# CODEC_1_OUTPUT_BUFFER.net
KiCad netlist of a schematic drawn in Altium Designer
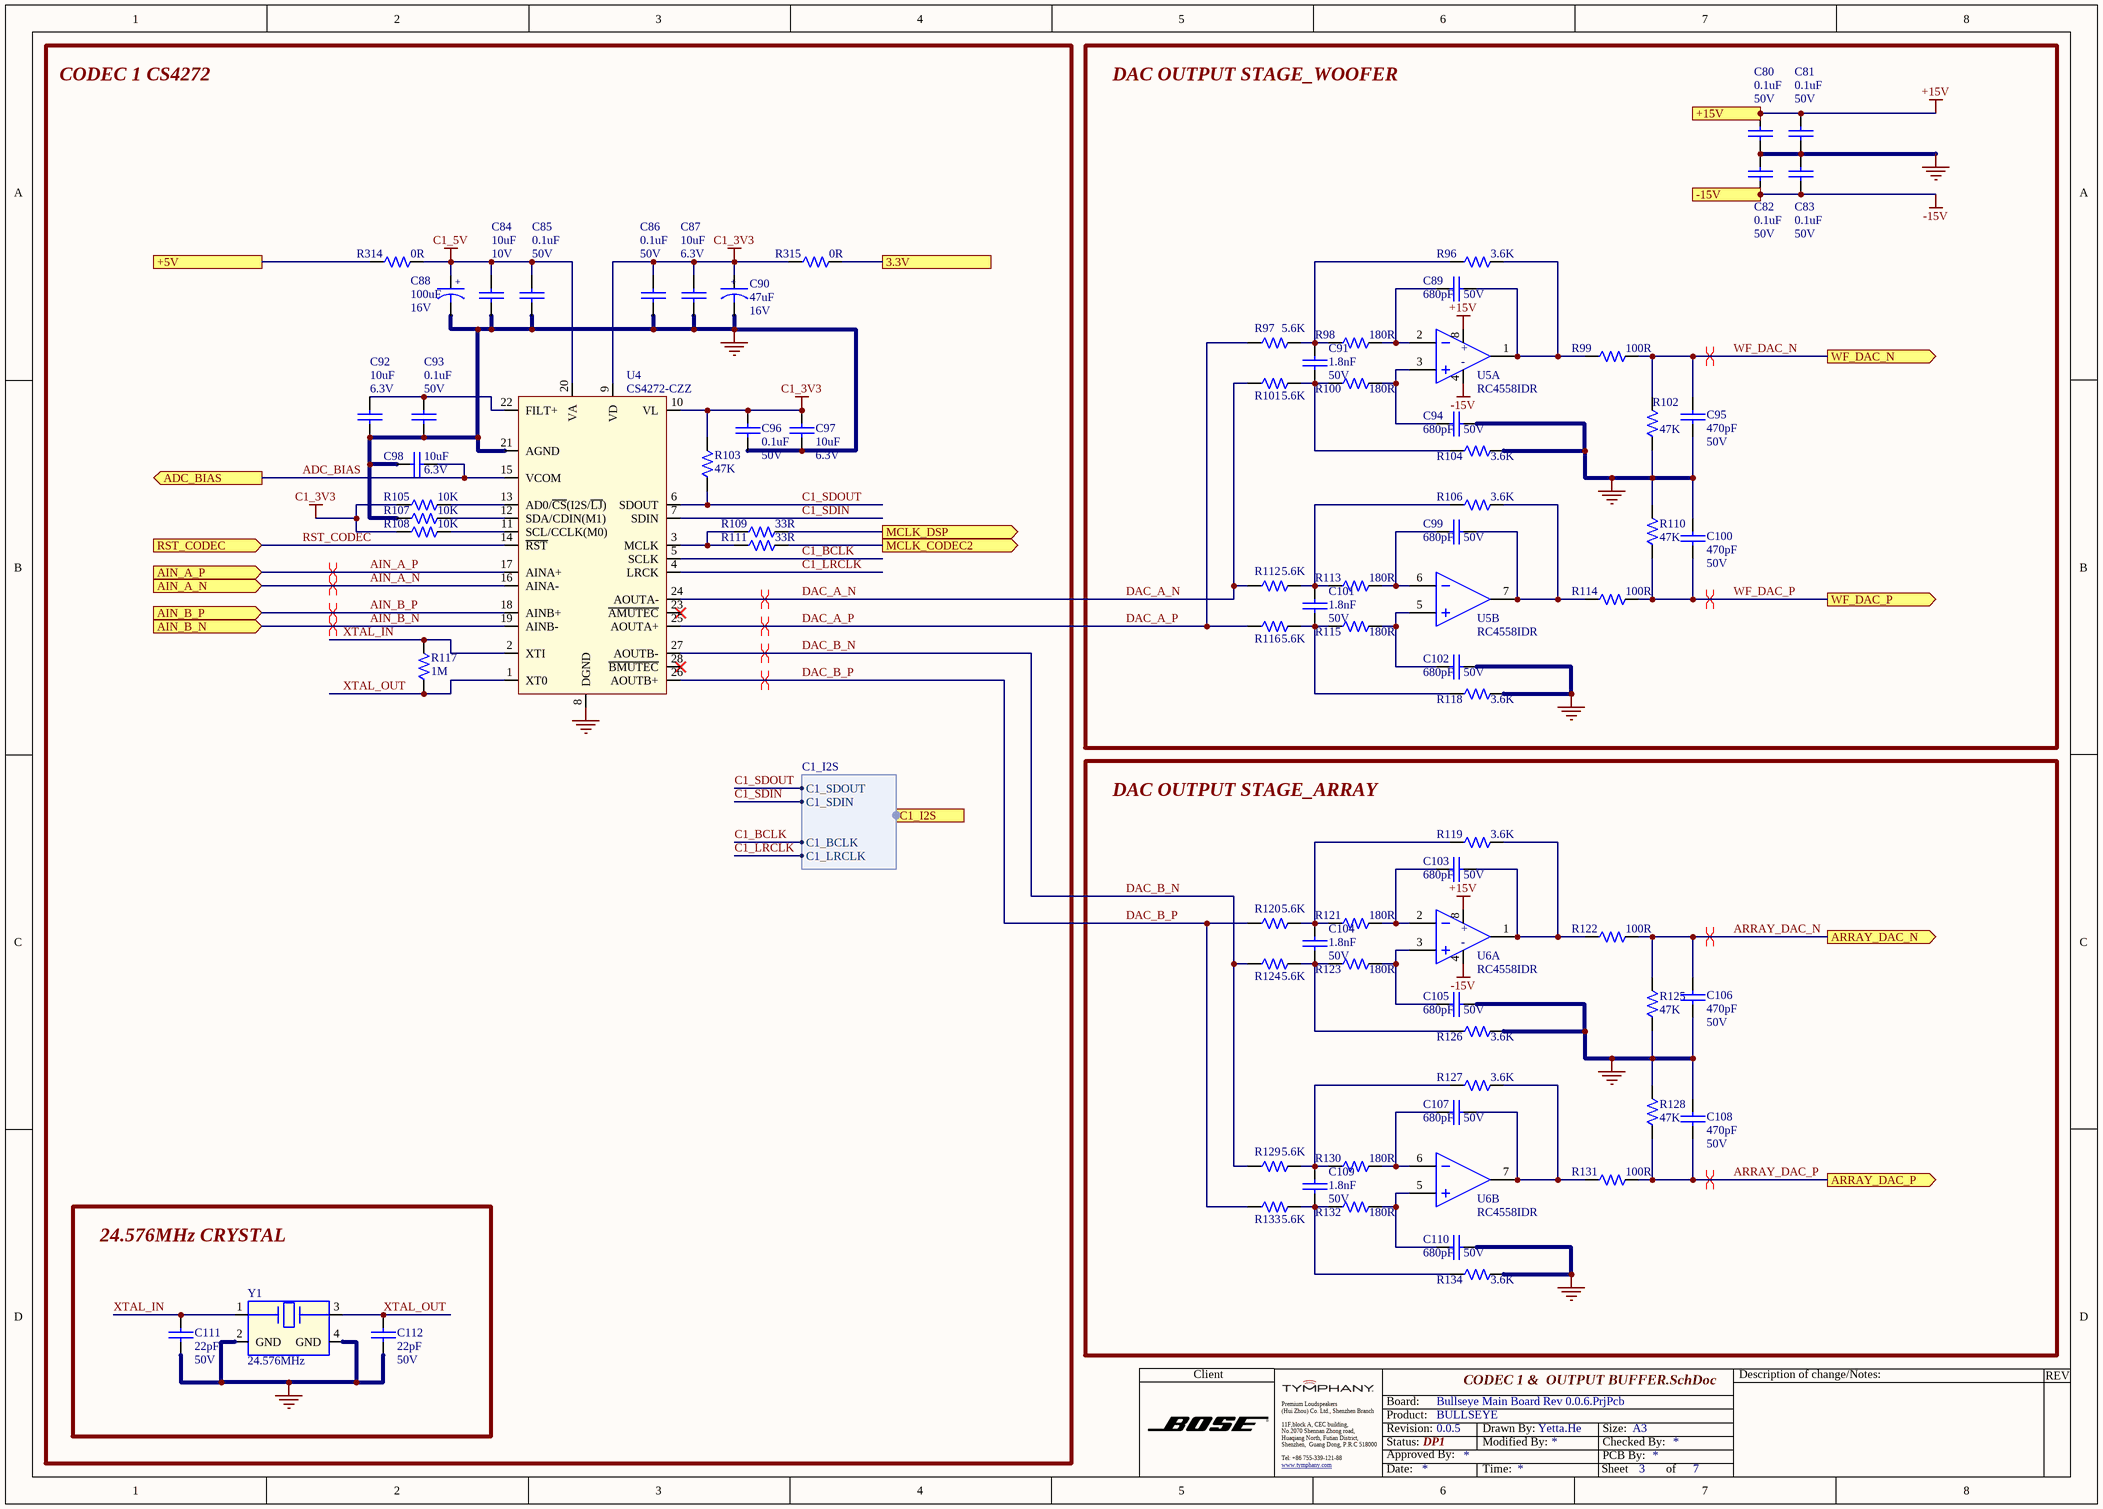
[diagram p0: CODEC 1 &  OUTPUT BUFFER.SchDoc]

(export (version "E")
  (design (tool "Eeschema 10.0.6"))
  (components
    (comp (ref "C80")
      (value "0.1uF")
      (footprint "CAPC0402-RW")
      (description "CAP, CER, 0.1uF, 10%, 50V, X7R, 0402, RoHS")
      (fields
        (field (name "TOLERANCE") "10%")
        (field (name "VOLTAGE") "50V")
        (field (name "Comment") "PWL456470-1040")
        (field (name "CREATE_NAME") "TOM@Deftronics")
      )
      (libsource (lib "P-Capacitors") (part "CAP0402 0.1uF 50V 10%"))
    )
    (comp (ref "C81")
      (value "0.1uF")
      (footprint "CAPC0402-RW")
      (description "CAP, CER, 0.1uF, 10%, 50V, X7R, 0402, RoHS")
      (fields
        (field (name "TOLERANCE") "10%")
        (field (name "VOLTAGE") "50V")
        (field (name "Comment") "PWL456470-1040")
        (field (name "CREATE_NAME") "TOM@Deftronics")
      )
      (libsource (lib "P-Capacitors") (part "CAP0402 0.1uF 50V 10%"))
    )
    (comp (ref "C82")
      (value "0.1uF")
      (footprint "CAPC0402-RW")
      (description "CAP, CER, 0.1uF, 10%, 50V, X7R, 0402, RoHS")
      (fields
        (field (name "TOLERANCE") "10%")
        (field (name "VOLTAGE") "50V")
        (field (name "Comment") "PWL456470-1040")
        (field (name "CREATE_NAME") "TOM@Deftronics")
      )
      (libsource (lib "P-Capacitors") (part "CAP0402 0.1uF 50V 10%"))
    )
    (comp (ref "C83")
      (value "0.1uF")
      (footprint "CAPC0402-RW")
      (description "CAP, CER, 0.1uF, 10%, 50V, X7R, 0402, RoHS")
      (fields
        (field (name "TOLERANCE") "10%")
        (field (name "VOLTAGE") "50V")
        (field (name "Comment") "PWL456470-1040")
        (field (name "CREATE_NAME") "TOM@Deftronics")
      )
      (libsource (lib "P-Capacitors") (part "CAP0402 0.1uF 50V 10%"))
    )
    (comp (ref "C84")
      (value "10uF")
      (footprint "CAPC0603-RW")
      (description "CAP 10UF 10V +-20% 0603X5R SAMSUNG L")
      (fields
        (field (name "MFG") "SAMSUNG")
        (field (name "TOLERANCE") "20%,")
        (field (name "VOLTAGE") "10V")
        (field (name "CREATE_NAME") "Nathan")
      )
      (libsource (lib "P-Capacitors") (part "CAP0603 10uF 10V 20%_X5R_SAMSUNG"))
    )
    (comp (ref "C85")
      (value "0.1uF")
      (footprint "CAPC0402-RW")
      (description "CAP X7R .10UF 50V +-10% 0402 WALSIN L")
      (fields
        (field (name "TOLERANCE") "10%")
        (field (name "VOLTAGE") "50V")
        (field (name "Comment") "PWL456470-1040")
        (field (name "CREATE_NAME") "TOM@Deftronics")
      )
      (libsource (lib "P-Capacitors") (part "CAP0402 0.1uF 50V 10%"))
    )
    (comp (ref "C86")
      (value "0.1uF")
      (footprint "CAPC0402-RW")
      (description "CAP X7R .10UF 50V +-10% 0402 WALSIN L")
      (fields
        (field (name "TOLERANCE") "10%")
        (field (name "VOLTAGE") "50V")
        (field (name "Comment") "PWL456470-1040")
        (field (name "CREATE_NAME") "TOM@Deftronics")
      )
      (libsource (lib "P-Capacitors") (part "CAP0402 0.1uF 50V 10%"))
    )
    (comp (ref "C87")
      (value "10uF")
      (footprint "CAPC0603-RW")
      (description "CAP X5R 10UF 6.3V +-10% 0603 SAMSUN L")
      (fields
        (field (name "MFG") "SAMSUNG")
        (field (name "MFG PART") "CL10A106KQ8NNNC")
        (field (name "VOLTAGE") "6.3V")
        (field (name "CREATE_NAME") "Nathan")
      )
      (libsource (lib "P-Capacitors") (part "CAP0603 10uF 6.3V 10%_X5R_SAMSUNG"))
    )
    (comp (ref "C88")
      (value "100uF")
      (footprint "CASE - D")
      (description "E 100UF 16V +-20% 6.3*5. VZH101M1C L")
      (fields
        (field (name "MFG") "LELON")
        (field (name "MFG PART") "VZH101M1CTR-0605")
        (field (name "VOLTAGE") "16V")
        (field (name "CREATE_NAME") "Nathan")
      )
      (libsource (lib "P-Capacitors") (part "CAP E 100uF 16V 20% SMD-VZH101M1CTR-0605"))
    )
    (comp (ref "C89")
      (value "680pF")
      (footprint "CAPC0603-RW")
      (description "GP CHIP CAP 680pF 50V 5% 0603 NPO")
      (fields
        (field (name "TOLERANCE") "5%")
        (field (name "VOLTAGE") "50V")
        (field (name "Comment") "PXL410372-6810")
      )
      (libsource (lib "P-Capacitors") (part "CAP0603 680pF 50V 5% - PXL410372-6810"))
    )
    (comp (ref "C90")
      (value "47uF")
      (footprint "CASE - C5.7")
      (description "E 47UF 16V +-20% 5X6 VEJ470M1C K")
      (fields
        (field (name "MFG") "LELON")
        (field (name "MFG PART") "VEJ470M1CTR-0506")
        (field (name "VOLTAGE") "16V")
        (field (name "CREATE_NAME") "Nathan")
      )
      (libsource (lib "P-Capacitors") (part "CAP E 47uF 16V 20% SMD_VEJ470M1CTR-0506"))
    )
    (comp (ref "C91")
      (value "1.8nF")
      (footprint "CAPC0603-RW")
      (description "CHIP CAP 1.8nF 50V 10% 0603 X7R")
      (fields (field (name "MFG") "海能达") (field (name "TOLERANCE") "10%") (field (name "VOLTAGE") "50V"))
      (libsource (lib "P-Capacitors") (part "CAP0603 1.8nF 50V 10%"))
    )
    (comp (ref "C92")
      (value "10uF")
      (footprint "CAPC0603-RW")
      (description "CAP X5R 10UF 6.3V +-10% 0603 SAMSUN L")
      (fields
        (field (name "MFG") "SAMSUNG")
        (field (name "MFG PART") "CL10A106KQ8NNNC")
        (field (name "VOLTAGE") "6.3V")
        (field (name "CREATE_NAME") "Nathan")
      )
      (libsource (lib "P-Capacitors") (part "CAP0603 10uF 6.3V 10%_X5R_SAMSUNG"))
    )
    (comp (ref "C93")
      (value "0.1uF")
      (footprint "CAPC0402-RW")
      (description "CAP X7R .10UF 50V +-10% 0402 WALSIN L")
      (fields
        (field (name "TOLERANCE") "10%")
        (field (name "VOLTAGE") "50V")
        (field (name "Comment") "PWL456470-1040")
        (field (name "CREATE_NAME") "TOM@Deftronics")
      )
      (libsource (lib "P-Capacitors") (part "CAP0402 0.1uF 50V 10%"))
    )
    (comp (ref "C94")
      (value "680pF")
      (footprint "CAPC0603-RW")
      (description "GP CHIP CAP 680pF 50V 5% 0603 NPO")
      (fields
        (field (name "TOLERANCE") "5%")
        (field (name "VOLTAGE") "50V")
        (field (name "Comment") "PXL410372-6810")
      )
      (libsource (lib "P-Capacitors") (part "CAP0603 680pF 50V 5% - PXL410372-6810"))
    )
    (comp (ref "C95")
      (value "470pF")
      (footprint "CAPC0603-RW")
      (description "CAP NPO 470PF 50V +-2% 0603 WALSIN L")
      (fields
        (field (name "MFG") "WALSIN")
        (field (name "TOLERANCE") "2%")
        (field (name "VOLTAGE") "50V")
        (field (name "CREATE_NAME") "Nathan")
      )
      (libsource (lib "P-Capacitors") (part "CAP0603 470pF 50V 2%_NPO_WALSIN"))
    )
    (comp (ref "C96")
      (value "0.1uF")
      (footprint "CAPC0402-RW")
      (description "CAP X7R .10UF 50V +-10% 0402 WALSIN L")
      (fields
        (field (name "TOLERANCE") "10%")
        (field (name "VOLTAGE") "50V")
        (field (name "Comment") "PWL456470-1040")
        (field (name "CREATE_NAME") "TOM@Deftronics")
      )
      (libsource (lib "P-Capacitors") (part "CAP0402 0.1uF 50V 10%"))
    )
    (comp (ref "C97")
      (value "10uF")
      (footprint "CAPC0603-RW")
      (description "CAP X5R 10UF 6.3V +-10% 0603 SAMSUN L")
      (fields
        (field (name "MFG") "SAMSUNG")
        (field (name "MFG PART") "CL10A106KQ8NNNC")
        (field (name "VOLTAGE") "6.3V")
        (field (name "CREATE_NAME") "Nathan")
      )
      (libsource (lib "P-Capacitors") (part "CAP0603 10uF 6.3V 10%_X5R_SAMSUNG"))
    )
    (comp (ref "C98")
      (value "10uF")
      (footprint "CAPC0603-RW")
      (description "CAP X5R 10UF 6.3V +-10% 0603 SAMSUN L")
      (fields
        (field (name "MFG") "SAMSUNG")
        (field (name "MFG PART") "CL10A106KQ8NNNC")
        (field (name "VOLTAGE") "6.3V")
        (field (name "CREATE_NAME") "Nathan")
      )
      (libsource (lib "P-Capacitors") (part "CAP0603 10uF 6.3V 10%_X5R_SAMSUNG"))
    )
    (comp (ref "C99")
      (value "680pF")
      (footprint "CAPC0603-RW")
      (description "GP CHIP CAP 680pF 50V 5% 0603 NPO")
      (fields
        (field (name "TOLERANCE") "5%")
        (field (name "VOLTAGE") "50V")
        (field (name "Comment") "PXL410372-6810")
      )
      (libsource (lib "P-Capacitors") (part "CAP0603 680pF 50V 5% - PXL410372-6810"))
    )
    (comp (ref "C100")
      (value "470pF")
      (footprint "CAPC0603-RW")
      (description "CAP NPO 470PF 50V +-2% 0603 WALSIN L")
      (fields
        (field (name "MFG") "WALSIN")
        (field (name "TOLERANCE") "2%")
        (field (name "VOLTAGE") "50V")
        (field (name "CREATE_NAME") "Nathan")
      )
      (libsource (lib "P-Capacitors") (part "CAP0603 470pF 50V 2%_NPO_WALSIN"))
    )
    (comp (ref "C101")
      (value "1.8nF")
      (footprint "CAPC0603-RW")
      (description "CHIP CAP 1.8nF 50V 10% 0603 X7R")
      (fields (field (name "MFG") "海能达") (field (name "TOLERANCE") "10%") (field (name "VOLTAGE") "50V"))
      (libsource (lib "P-Capacitors") (part "CAP0603 1.8nF 50V 10%"))
    )
    (comp (ref "C102")
      (value "680pF")
      (footprint "CAPC0603-RW")
      (description "GP CHIP CAP 680pF 50V 5% 0603 NPO")
      (fields
        (field (name "TOLERANCE") "5%")
        (field (name "VOLTAGE") "50V")
        (field (name "Comment") "PXL410372-6810")
      )
      (libsource (lib "P-Capacitors") (part "CAP0603 680pF 50V 5% - PXL410372-6810"))
    )
    (comp (ref "C103")
      (value "680pF")
      (footprint "CAPC0603-RW")
      (description "GP CHIP CAP 680pF 50V 5% 0603 NPO")
      (fields
        (field (name "TOLERANCE") "5%")
        (field (name "VOLTAGE") "50V")
        (field (name "Comment") "PXL410372-6810")
      )
      (libsource (lib "P-Capacitors") (part "CAP0603 680pF 50V 5% - PXL410372-6810"))
    )
    (comp (ref "C104")
      (value "1.8nF")
      (footprint "CAPC0603-RW")
      (description "CHIP CAP 1.8nF 50V 10% 0603 X7R")
      (fields (field (name "MFG") "海能达") (field (name "TOLERANCE") "10%") (field (name "VOLTAGE") "50V"))
      (libsource (lib "P-Capacitors") (part "CAP0603 1.8nF 50V 10%"))
    )
    (comp (ref "C105")
      (value "680pF")
      (footprint "CAPC0603-RW")
      (description "GP CHIP CAP 680pF 50V 5% 0603 NPO")
      (fields
        (field (name "TOLERANCE") "5%")
        (field (name "VOLTAGE") "50V")
        (field (name "Comment") "PXL410372-6810")
      )
      (libsource (lib "P-Capacitors") (part "CAP0603 680pF 50V 5% - PXL410372-6810"))
    )
    (comp (ref "C106")
      (value "470pF")
      (footprint "CAPC0603-RW")
      (description "CAP NPO 470PF 50V +-2% 0603 WALSIN L")
      (fields
        (field (name "MFG") "WALSIN")
        (field (name "TOLERANCE") "2%")
        (field (name "VOLTAGE") "50V")
        (field (name "CREATE_NAME") "Nathan")
      )
      (libsource (lib "P-Capacitors") (part "CAP0603 470pF 50V 2%_NPO_WALSIN"))
    )
    (comp (ref "C107")
      (value "680pF")
      (footprint "CAPC0603-RW")
      (description "GP CHIP CAP 680pF 50V 5% 0603 NPO")
      (fields
        (field (name "TOLERANCE") "5%")
        (field (name "VOLTAGE") "50V")
        (field (name "Comment") "PXL410372-6810")
      )
      (libsource (lib "P-Capacitors") (part "CAP0603 680pF 50V 5% - PXL410372-6810"))
    )
    (comp (ref "C108")
      (value "470pF")
      (footprint "CAPC0603-RW")
      (description "CAP NPO 470PF 50V +-2% 0603 WALSIN L")
      (fields
        (field (name "MFG") "WALSIN")
        (field (name "TOLERANCE") "2%")
        (field (name "VOLTAGE") "50V")
        (field (name "CREATE_NAME") "Nathan")
      )
      (libsource (lib "P-Capacitors") (part "CAP0603 470pF 50V 2%_NPO_WALSIN"))
    )
    (comp (ref "C109")
      (value "1.8nF")
      (footprint "CAPC0603-RW")
      (description "CHIP CAP 1.8nF 50V 10% 0603 X7R")
      (fields (field (name "MFG") "海能达") (field (name "TOLERANCE") "10%") (field (name "VOLTAGE") "50V"))
      (libsource (lib "P-Capacitors") (part "CAP0603 1.8nF 50V 10%"))
    )
    (comp (ref "C110")
      (value "680pF")
      (footprint "CAPC0603-RW")
      (description "GP CHIP CAP 680pF 50V 5% 0603 NPO")
      (fields
        (field (name "TOLERANCE") "5%")
        (field (name "VOLTAGE") "50V")
        (field (name "Comment") "PXL410372-6810")
      )
      (libsource (lib "P-Capacitors") (part "CAP0603 680pF 50V 5% - PXL410372-6810"))
    )
    (comp (ref "C111")
      (value "22pF")
      (footprint "CAPC0402-RW")
      (description "CHIP CAP 5% 50V 0402 NPO 22pF")
      (fields
        (field (name "TOLERANCE") "5%")
        (field (name "VOLTAGE") "50V")
        (field (name "Comment") "PWL410370-2200")
        (field (name "CREATE_NAME") "GordonL@Deftronics")
      )
      (libsource (lib "P-Capacitors") (part "CAP0402 22pF 50V 5%"))
    )
    (comp (ref "C112")
      (value "22pF")
      (footprint "CAPC0402-RW")
      (description "CHIP CAP 5% 50V 0402 NPO 22pF")
      (fields
        (field (name "TOLERANCE") "5%")
        (field (name "VOLTAGE") "50V")
        (field (name "Comment") "PWL410370-2200")
        (field (name "CREATE_NAME") "GordonL@Deftronics")
      )
      (libsource (lib "P-Capacitors") (part "CAP0402 22pF 50V 5%"))
    )
    (comp (ref "R96")
      (value "3.6K")
      (footprint "0603-RW")
      (description "GP CHIP RES. 3.6K OHM 1/10W 1% 0603")
      (fields (field (name "POWER") "1/10W") (field (name "Comment") "QCF011030-3601"))
      (libsource (lib "Q-Resistors") (part "RES0603 1/10W 1% 3.6K OHM"))
    )
    (comp (ref "R97")
      (value "5.6K")
      (footprint "0603-RW")
      (description "GP CHIP RES. 5.6K OHM 1/10W 1% 0603")
      (fields (field (name "POWER") "1/10W") (field (name "Comment") "QCF011030-5601"))
      (libsource (lib "Q-Resistors") (part "RES0603 1/10W 1% 5.6K OHM"))
    )
    (comp (ref "R98")
      (value "180R")
      (footprint "0603-RW")
      (description "CHIP RES. 180 OHM 1/10W 1% 0603")
      (fields (field (name "POWER") "1/10W") (field (name "Comment") "QCF011030-1800"))
      (libsource (lib "Q-Resistors") (part "RES0603 1/10W 1% 180 OHM"))
    )
    (comp (ref "R99")
      (value "100R")
      (footprint "0603-RW")
      (description "CHIP 100 OHM 100PPM +-1% 0603 WALS L")
      (fields (field (name "POWER") "1/10W") (field (name "MFG") "WALSIN (華新)"))
      (libsource (lib "Q-Resistors") (part "RES0603 1/10W 1% 100 OHM"))
    )
    (comp (ref "R100")
      (value "180R")
      (footprint "0603-RW")
      (description "CHIP RES. 180 OHM 1/10W 1% 0603")
      (fields (field (name "POWER") "1/10W") (field (name "Comment") "QCF011030-1800"))
      (libsource (lib "Q-Resistors") (part "RES0603 1/10W 1% 180 OHM"))
    )
    (comp (ref "R101")
      (value "5.6K")
      (footprint "0603-RW")
      (description "GP CHIP RES. 5.6K OHM 1/10W 1% 0603")
      (fields (field (name "POWER") "1/10W") (field (name "Comment") "QCF011030-5601"))
      (libsource (lib "Q-Resistors") (part "RES0603 1/10W 1% 5.6K OHM"))
    )
    (comp (ref "R102")
      (value "47K")
      (footprint "0603-RW")
      (description "GP CHIP RES. 47K OHM 1/10W 1% 0603")
      (fields (field (name "POWER") "1/10W") (field (name "Comment") "QCF011030-4702"))
      (libsource (lib "Q-Resistors") (part "RES0603 1/10W 1% 47K OHM"))
    )
    (comp (ref "R103")
      (value "47K")
      (footprint "0603-RW")
      (description "GP CHIP RES. 47K OHM 1/10W 1% 0603")
      (fields (field (name "POWER") "1/10W") (field (name "Comment") "QCF011030-4702"))
      (libsource (lib "Q-Resistors") (part "RES0603 1/10W 1% 47K OHM"))
    )
    (comp (ref "R104")
      (value "3.6K")
      (footprint "0603-RW")
      (description "GP CHIP RES. 3.6K OHM 1/10W 1% 0603")
      (fields (field (name "POWER") "1/10W") (field (name "Comment") "QCF011030-3601"))
      (libsource (lib "Q-Resistors") (part "RES0603 1/10W 1% 3.6K OHM"))
    )
    (comp (ref "R105")
      (value "10K")
      (footprint "0402-RW")
      (description "CHIP RES 10K OHM 1/16W 1% 0402")
      (fields (field (name "POWER") "1/16W") (field (name "MFG") "WALSIN"))
      (libsource (lib "Q-Resistors") (part "RES0402 1/16W 1% 10K OHM"))
    )
    (comp (ref "R106")
      (value "3.6K")
      (footprint "0603-RW")
      (description "GP CHIP RES. 3.6K OHM 1/10W 1% 0603")
      (fields (field (name "POWER") "1/10W") (field (name "Comment") "QCF011030-3601"))
      (libsource (lib "Q-Resistors") (part "RES0603 1/10W 1% 3.6K OHM"))
    )
    (comp (ref "R107")
      (value "10K")
      (footprint "0402-RW")
      (description "CHIP RES 10K OHM 1/16W 1% 0402")
      (fields (field (name "POWER") "1/16W") (field (name "MFG") "WALSIN"))
      (libsource (lib "Q-Resistors") (part "RES0402 1/16W 1% 10K OHM"))
    )
    (comp (ref "R108")
      (value "10K")
      (footprint "0402-RW")
      (description "CHIP RES 10K OHM 1/16W 1% 0402")
      (fields (field (name "POWER") "1/16W") (field (name "MFG") "WALSIN"))
      (libsource (lib "Q-Resistors") (part "RES0402 1/16W 1% 10K OHM"))
    )
    (comp (ref "R109")
      (value "33R")
      (footprint "0402-RW")
      (description "CHIP RES 33 OHM 1/16W 1% 0402")
      (fields (field (name "POWER") "1/16W") (field (name "MFG") "WALSIN"))
      (libsource (lib "Q-Resistors") (part "RES0402 1/16W 1% 33 OHM"))
    )
    (comp (ref "R110")
      (value "47K")
      (footprint "0603-RW")
      (description "GP CHIP RES. 47K OHM 1/10W 1% 0603")
      (fields (field (name "POWER") "1/10W") (field (name "Comment") "QCF011030-4702"))
      (libsource (lib "Q-Resistors") (part "RES0603 1/10W 1% 47K OHM"))
    )
    (comp (ref "R111")
      (value "33R")
      (footprint "0402-RW")
      (description "CHIP RES 33 OHM 1/16W 1% 0402")
      (fields (field (name "POWER") "1/16W") (field (name "MFG") "WALSIN"))
      (libsource (lib "Q-Resistors") (part "RES0402 1/16W 1% 33 OHM"))
    )
    (comp (ref "R112")
      (value "5.6K")
      (footprint "0603-RW")
      (description "GP CHIP RES. 5.6K OHM 1/10W 1% 0603")
      (fields (field (name "POWER") "1/10W") (field (name "Comment") "QCF011030-5601"))
      (libsource (lib "Q-Resistors") (part "RES0603 1/10W 1% 5.6K OHM"))
    )
    (comp (ref "R113")
      (value "180R")
      (footprint "0603-RW")
      (description "CHIP RES. 180 OHM 1/10W 1% 0603")
      (fields (field (name "POWER") "1/10W") (field (name "Comment") "QCF011030-1800"))
      (libsource (lib "Q-Resistors") (part "RES0603 1/10W 1% 180 OHM"))
    )
    (comp (ref "R114")
      (value "100R")
      (footprint "0603-RW")
      (description "CHIP 100 OHM 100PPM +-1% 0603 WALS L")
      (fields (field (name "POWER") "1/10W") (field (name "MFG") "WALSIN (華新)"))
      (libsource (lib "Q-Resistors") (part "RES0603 1/10W 1% 100 OHM"))
    )
    (comp (ref "R115")
      (value "180R")
      (footprint "0603-RW")
      (description "CHIP RES. 180 OHM 1/10W 1% 0603")
      (fields (field (name "POWER") "1/10W") (field (name "Comment") "QCF011030-1800"))
      (libsource (lib "Q-Resistors") (part "RES0603 1/10W 1% 180 OHM"))
    )
    (comp (ref "R116")
      (value "5.6K")
      (footprint "0603-RW")
      (description "GP CHIP RES. 5.6K OHM 1/10W 1% 0603")
      (fields (field (name "POWER") "1/10W") (field (name "Comment") "QCF011030-5601"))
      (libsource (lib "Q-Resistors") (part "RES0603 1/10W 1% 5.6K OHM"))
    )
    (comp (ref "R117")
      (value "1M")
      (footprint "0402-RW")
      (description "CHIP RES 1M OHM 1/16W 1% 0402")
      (fields (field (name "POWER") "1/16W") (field (name "MFG") "WALSIN"))
      (libsource (lib "Q-Resistors") (part "RES0402 1/16W 1% 1M OHM"))
    )
    (comp (ref "R118")
      (value "3.6K")
      (footprint "0603-RW")
      (description "GP CHIP RES. 3.6K OHM 1/10W 1% 0603")
      (fields (field (name "POWER") "1/10W") (field (name "Comment") "QCF011030-3601"))
      (libsource (lib "Q-Resistors") (part "RES0603 1/10W 1% 3.6K OHM"))
    )
    (comp (ref "R119")
      (value "3.6K")
      (footprint "0603-RW")
      (description "GP CHIP RES. 3.6K OHM 1/10W 1% 0603")
      (fields (field (name "POWER") "1/10W") (field (name "Comment") "QCF011030-3601"))
      (libsource (lib "Q-Resistors") (part "RES0603 1/10W 1% 3.6K OHM"))
    )
    (comp (ref "R120")
      (value "5.6K")
      (footprint "0603-RW")
      (description "GP CHIP RES. 5.6K OHM 1/10W 1% 0603")
      (fields (field (name "POWER") "1/10W") (field (name "Comment") "QCF011030-5601"))
      (libsource (lib "Q-Resistors") (part "RES0603 1/10W 1% 5.6K OHM"))
    )
    (comp (ref "R121")
      (value "180R")
      (footprint "0603-RW")
      (description "CHIP RES. 180 OHM 1/10W 1% 0603")
      (fields (field (name "POWER") "1/10W") (field (name "Comment") "QCF011030-1800"))
      (libsource (lib "Q-Resistors") (part "RES0603 1/10W 1% 180 OHM"))
    )
    (comp (ref "R122")
      (value "100R")
      (footprint "0603-RW")
      (description "CHIP 100 OHM 100PPM +-1% 0603 WALS L")
      (fields (field (name "POWER") "1/10W") (field (name "MFG") "WALSIN (華新)"))
      (libsource (lib "Q-Resistors") (part "RES0603 1/10W 1% 100 OHM"))
    )
    (comp (ref "R123")
      (value "180R")
      (footprint "0603-RW")
      (description "CHIP RES. 180 OHM 1/10W 1% 0603")
      (fields (field (name "POWER") "1/10W") (field (name "Comment") "QCF011030-1800"))
      (libsource (lib "Q-Resistors") (part "RES0603 1/10W 1% 180 OHM"))
    )
    (comp (ref "R124")
      (value "5.6K")
      (footprint "0603-RW")
      (description "GP CHIP RES. 5.6K OHM 1/10W 1% 0603")
      (fields (field (name "POWER") "1/10W") (field (name "Comment") "QCF011030-5601"))
      (libsource (lib "Q-Resistors") (part "RES0603 1/10W 1% 5.6K OHM"))
    )
    (comp (ref "R125")
      (value "47K")
      (footprint "0603-RW")
      (description "GP CHIP RES. 47K OHM 1/10W 1% 0603")
      (fields (field (name "POWER") "1/10W") (field (name "Comment") "QCF011030-4702"))
      (libsource (lib "Q-Resistors") (part "RES0603 1/10W 1% 47K OHM"))
    )
    (comp (ref "R126")
      (value "3.6K")
      (footprint "0603-RW")
      (description "GP CHIP RES. 3.6K OHM 1/10W 1% 0603")
      (fields (field (name "POWER") "1/10W") (field (name "Comment") "QCF011030-3601"))
      (libsource (lib "Q-Resistors") (part "RES0603 1/10W 1% 3.6K OHM"))
    )
    (comp (ref "R127")
      (value "3.6K")
      (footprint "0603-RW")
      (description "GP CHIP RES. 3.6K OHM 1/10W 1% 0603")
      (fields (field (name "POWER") "1/10W") (field (name "Comment") "QCF011030-3601"))
      (libsource (lib "Q-Resistors") (part "RES0603 1/10W 1% 3.6K OHM"))
    )
    (comp (ref "R128")
      (value "47K")
      (footprint "0603-RW")
      (description "GP CHIP RES. 47K OHM 1/10W 1% 0603")
      (fields (field (name "POWER") "1/10W") (field (name "Comment") "QCF011030-4702"))
      (libsource (lib "Q-Resistors") (part "RES0603 1/10W 1% 47K OHM"))
    )
    (comp (ref "R129")
      (value "5.6K")
      (footprint "0603-RW")
      (description "GP CHIP RES. 5.6K OHM 1/10W 1% 0603")
      (fields (field (name "POWER") "1/10W") (field (name "Comment") "QCF011030-5601"))
      (libsource (lib "Q-Resistors") (part "RES0603 1/10W 1% 5.6K OHM"))
    )
    (comp (ref "R130")
      (value "180R")
      (footprint "0603-RW")
      (description "CHIP RES. 180 OHM 1/10W 1% 0603")
      (fields (field (name "POWER") "1/10W") (field (name "Comment") "QCF011030-1800"))
      (libsource (lib "Q-Resistors") (part "RES0603 1/10W 1% 180 OHM"))
    )
    (comp (ref "R131")
      (value "100R")
      (footprint "0603-RW")
      (description "CHIP 100 OHM 100PPM +-1% 0603 WALS L")
      (fields (field (name "POWER") "1/10W") (field (name "MFG") "WALSIN (華新)"))
      (libsource (lib "Q-Resistors") (part "RES0603 1/10W 1% 100 OHM"))
    )
    (comp (ref "R132")
      (value "180R")
      (footprint "0603-RW")
      (description "CHIP RES. 180 OHM 1/10W 1% 0603")
      (fields (field (name "POWER") "1/10W") (field (name "Comment") "QCF011030-1800"))
      (libsource (lib "Q-Resistors") (part "RES0603 1/10W 1% 180 OHM"))
    )
    (comp (ref "R133")
      (value "5.6K")
      (footprint "0603-RW")
      (description "GP CHIP RES. 5.6K OHM 1/10W 1% 0603")
      (fields (field (name "POWER") "1/10W") (field (name "Comment") "QCF011030-5601"))
      (libsource (lib "Q-Resistors") (part "RES0603 1/10W 1% 5.6K OHM"))
    )
    (comp (ref "R134")
      (value "3.6K")
      (footprint "0603-RW")
      (description "GP CHIP RES. 3.6K OHM 1/10W 1% 0603")
      (fields (field (name "POWER") "1/10W") (field (name "Comment") "QCF011030-3601"))
      (libsource (lib "Q-Resistors") (part "RES0603 1/10W 1% 3.6K OHM"))
    )
    (comp (ref "R314")
      (value "0R")
      (footprint "0603-RW")
      (description "CHIP 0 OHM 0 OHM 0 OHM 0603 WALSIN L")
      (fields (field (name "POWER") "1/10W") (field (name "MFG PART") "WR06X000PTL"))
      (libsource (lib "Q-Resistors") (part "RES0603 1/10W 0 OHM_WALSIN"))
    )
    (comp (ref "R315")
      (value "0R")
      (footprint "0603-RW")
      (description "CHIP 0 OHM 0 OHM 0 OHM 0603 WALSIN L")
      (fields (field (name "POWER") "1/10W") (field (name "MFG PART") "WR06X000PTL"))
      (libsource (lib "Q-Resistors") (part "RES0603 1/10W 0 OHM_WALSIN"))
    )
    (comp (ref "U4")
      (value "RCI004272-0001")
      (footprint "TSSOP28")
      (description "IC CODEC CS4272-CZZ TSSOP-28")
      (fields
        (field (name "MFG") "CIRRUS LOGIC")
        (field (name "MFG PART") "CS4272-CZZ")
        (field (name "CREATE_NAME") "GordonL@Deftronics")
      )
      (libsource (lib "R-Semiconductors") (part "CS4272-CZZ"))
    )
    (comp (ref "U5")
      (value "T610500019101")
      (footprint "D(R-PDSO-G8)")
      (description "OP RC4558IDR SOP-8 TI G")
      (fields
        (field (name "MFG") "TI")
        (field (name "MFG PART") "RC4558IDR")
        (field (name "CREATE_NAME") "Nathan")
      )
      (libsource (lib "R-Semiconductors") (part "RC4558IDR"))
    )
    (comp (ref "U6")
      (value "T610500019101")
      (footprint "D(R-PDSO-G8)")
      (description "OP RC4558IDR SOP-8 TI G")
      (fields
        (field (name "MFG") "TI")
        (field (name "MFG PART") "RC4558IDR")
        (field (name "CREATE_NAME") "Nathan")
      )
      (libsource (lib "R-Semiconductors") (part "RC4558IDR"))
    )
    (comp (ref "Y1")
      (value "T690900003500")
      (footprint "SMD2520")
      (description "CRYSTAL 24.576MH SMD SIWARD XTL571200-F98-048 G")
      (fields
        (field (name "MFG PART") "XTL571200-F98-048")
        (field (name "MFG") "SIWARD")
        (field (name "FREQUENCY") "24.576MHz")
        (field (name "CREATE_NAME") "Nathan")
      )
      (libsource (lib "J-Crystal") (part "CRY 24.576MHz_XTL571200-F98-048"))
    )
  )
  (nets
    (net (code "2") (name "+15V") (class "Default")
      (node (ref "C80") (pin "1") (pinfunction "1_1") (pintype "passive"))
      (node (ref "C81") (pin "1") (pinfunction "1_1") (pintype "passive"))
      (node (ref "U5") (pin "8") (pinfunction "VCC+_8") (pintype "passive"))
      (node (ref "U6") (pin "8") (pinfunction "VCC+_8") (pintype "passive"))
    )
    (net (code "3") (name "-15V") (class "Default")
      (node (ref "C82") (pin "2") (pinfunction "2_2") (pintype "passive"))
      (node (ref "C83") (pin "2") (pinfunction "2_2") (pintype "passive"))
      (node (ref "U5") (pin "4") (pinfunction "VCC-_4") (pintype "passive"))
      (node (ref "U6") (pin "4") (pinfunction "VCC-_4") (pintype "passive"))
    )
    (net (code "4") (name "/+5V") (class "Default")
      (node (ref "R314") (pin "1") (pinfunction "1_1") (pintype "passive"))
    )
    (net (code "5") (name "/3.3V") (class "Default")
      (node (ref "R315") (pin "2") (pinfunction "2_2") (pintype "passive"))
    )
    (net (code "6") (name "/ADC_BIAS") (class "Default")
      (node (ref "C98") (pin "1") (pinfunction "1_1") (pintype "passive"))
      (node (ref "U4") (pin "15") (pinfunction "VCOM_15") (pintype "passive"))
    )
    (net (code "7") (name "/AIN_A_N") (class "Default")
      (node (ref "U4") (pin "16") (pinfunction "AINA-_16") (pintype "passive"))
    )
    (net (code "8") (name "/AIN_A_P") (class "Default")
      (node (ref "U4") (pin "17") (pinfunction "AINA+_17") (pintype "passive"))
    )
    (net (code "9") (name "/AIN_B_N") (class "Default")
      (node (ref "U4") (pin "19") (pinfunction "AINB-_19") (pintype "passive"))
    )
    (net (code "10") (name "/AIN_B_P") (class "Default")
      (node (ref "U4") (pin "18") (pinfunction "AINB+_18") (pintype "passive"))
    )
    (net (code "11") (name "/ARRAY_DAC_N") (class "Default")
      (node (ref "C106") (pin "1") (pinfunction "1_1") (pintype "passive"))
      (node (ref "R122") (pin "2") (pinfunction "2_2") (pintype "passive"))
      (node (ref "R125") (pin "2") (pinfunction "2_2") (pintype "passive"))
    )
    (net (code "12") (name "/ARRAY_DAC_P") (class "Default")
      (node (ref "C108") (pin "2") (pinfunction "2_2") (pintype "passive"))
      (node (ref "R128") (pin "1") (pinfunction "1_1") (pintype "passive"))
      (node (ref "R131") (pin "2") (pinfunction "2_2") (pintype "passive"))
    )
    (net (code "13") (name "/C1_BCLK") (class "Default")
      (node (ref "U4") (pin "5") (pinfunction "SCLK_5") (pintype "passive"))
    )
    (net (code "14") (name "/C1_LRCLK") (class "Default")
      (node (ref "U4") (pin "4") (pinfunction "LRCK_4") (pintype "passive"))
    )
    (net (code "15") (name "/C1_SDIN") (class "Default")
      (node (ref "U4") (pin "7") (pinfunction "SDIN_7") (pintype "passive"))
    )
    (net (code "16") (name "/C1_SDOUT") (class "Default")
      (node (ref "R103") (pin "1") (pinfunction "1_1") (pintype "passive"))
      (node (ref "U4") (pin "6") (pinfunction "SDOUT_6") (pintype "passive"))
    )
    (net (code "17") (name "/DAC_A_N") (class "Default")
      (node (ref "R101") (pin "1") (pinfunction "1_1") (pintype "passive"))
      (node (ref "R112") (pin "1") (pinfunction "1_1") (pintype "passive"))
      (node (ref "U4") (pin "24") (pinfunction "AOUTA-_24") (pintype "passive"))
    )
    (net (code "18") (name "/DAC_A_P") (class "Default")
      (node (ref "R116") (pin "1") (pinfunction "1_1") (pintype "passive"))
      (node (ref "R97") (pin "1") (pinfunction "1_1") (pintype "passive"))
      (node (ref "U4") (pin "25") (pinfunction "AOUTA+_25") (pintype "passive"))
    )
    (net (code "19") (name "/DAC_B_N") (class "Default")
      (node (ref "R124") (pin "1") (pinfunction "1_1") (pintype "passive"))
      (node (ref "R129") (pin "1") (pinfunction "1_1") (pintype "passive"))
      (node (ref "U4") (pin "27") (pinfunction "AOUTB-_27") (pintype "passive"))
    )
    (net (code "20") (name "/DAC_B_P") (class "Default")
      (node (ref "R120") (pin "1") (pinfunction "1_1") (pintype "passive"))
      (node (ref "R133") (pin "1") (pinfunction "1_1") (pintype "passive"))
      (node (ref "U4") (pin "26") (pinfunction "AOUTB+_26") (pintype "passive"))
    )
    (net (code "21") (name "/MCLK_CODEC2") (class "Default")
      (node (ref "R111") (pin "2") (pinfunction "2_2") (pintype "passive"))
    )
    (net (code "22") (name "/MCLK_DSP") (class "Default")
      (node (ref "R109") (pin "2") (pinfunction "2_2") (pintype "passive"))
    )
    (net (code "23") (name "/RST_CODEC") (class "Default")
      (node (ref "U4") (pin "14") (pinfunction "~{RST}_14") (pintype "passive"))
    )
    (net (code "24") (name "/WF_DAC_N") (class "Default")
      (node (ref "C95") (pin "1") (pinfunction "1_1") (pintype "passive"))
      (node (ref "R102") (pin "2") (pinfunction "2_2") (pintype "passive"))
      (node (ref "R99") (pin "2") (pinfunction "2_2") (pintype "passive"))
    )
    (net (code "25") (name "/WF_DAC_P") (class "Default")
      (node (ref "C100") (pin "2") (pinfunction "2_2") (pintype "passive"))
      (node (ref "R110") (pin "1") (pinfunction "1_1") (pintype "passive"))
      (node (ref "R114") (pin "2") (pinfunction "2_2") (pintype "passive"))
    )
    (net (code "26") (name "/XTAL_IN") (class "Default")
      (node (ref "C111") (pin "1") (pinfunction "1_1") (pintype "passive"))
      (node (ref "R117") (pin "2") (pinfunction "2_2") (pintype "passive"))
      (node (ref "U4") (pin "2") (pinfunction "XTI_2") (pintype "passive"))
      (node (ref "Y1") (pin "1") (pintype "passive"))
    )
    (net (code "27") (name "/XTAL_OUT") (class "Default")
      (node (ref "C112") (pin "1") (pinfunction "1_1") (pintype "passive"))
      (node (ref "R117") (pin "1") (pinfunction "1_1") (pintype "passive"))
      (node (ref "U4") (pin "1") (pinfunction "XT0_1") (pintype "passive"))
      (node (ref "Y1") (pin "3") (pintype "passive"))
    )
    (net (code "29") (name "C1_3V3") (class "Default")
      (node (ref "C86") (pin "1") (pinfunction "1_1") (pintype "passive"))
      (node (ref "C87") (pin "1") (pinfunction "1_1") (pintype "passive"))
      (node (ref "C90") (pin "1") (pinfunction "1_1") (pintype "passive"))
      (node (ref "C96") (pin "2") (pinfunction "2_2") (pintype "passive"))
      (node (ref "C97") (pin "2") (pinfunction "2_2") (pintype "passive"))
      (node (ref "R103") (pin "2") (pinfunction "2_2") (pintype "passive"))
      (node (ref "R105") (pin "1") (pinfunction "1_1") (pintype "passive"))
      (node (ref "R108") (pin "1") (pinfunction "1_1") (pintype "passive"))
      (node (ref "R315") (pin "1") (pinfunction "1_1") (pintype "passive"))
      (node (ref "U4") (pin "10") (pinfunction "VL_10") (pintype "passive"))
      (node (ref "U4") (pin "9") (pinfunction "VD_9") (pintype "passive"))
    )
    (net (code "30") (name "C1_5V") (class "Default")
      (node (ref "C84") (pin "1") (pinfunction "1_1") (pintype "passive"))
      (node (ref "C85") (pin "1") (pinfunction "1_1") (pintype "passive"))
      (node (ref "C88") (pin "1") (pinfunction "1_1") (pintype "passive"))
      (node (ref "R314") (pin "2") (pinfunction "2_2") (pintype "passive"))
      (node (ref "U4") (pin "20") (pinfunction "VA_20") (pintype "passive"))
    )
    (net (code "31") (name "GND") (class "Default")
      (node (ref "C100") (pin "1") (pinfunction "1_1") (pintype "passive"))
      (node (ref "C102") (pin "2") (pinfunction "2_2") (pintype "passive"))
      (node (ref "C105") (pin "2") (pinfunction "2_2") (pintype "passive"))
      (node (ref "C106") (pin "2") (pinfunction "2_2") (pintype "passive"))
      (node (ref "C108") (pin "1") (pinfunction "1_1") (pintype "passive"))
      (node (ref "C110") (pin "2") (pinfunction "2_2") (pintype "passive"))
      (node (ref "C111") (pin "2") (pinfunction "2_2") (pintype "passive"))
      (node (ref "C112") (pin "2") (pinfunction "2_2") (pintype "passive"))
      (node (ref "C80") (pin "2") (pinfunction "2_2") (pintype "passive"))
      (node (ref "C81") (pin "2") (pinfunction "2_2") (pintype "passive"))
      (node (ref "C82") (pin "1") (pinfunction "1_1") (pintype "passive"))
      (node (ref "C83") (pin "1") (pinfunction "1_1") (pintype "passive"))
      (node (ref "C84") (pin "2") (pinfunction "2_2") (pintype "passive"))
      (node (ref "C85") (pin "2") (pinfunction "2_2") (pintype "passive"))
      (node (ref "C86") (pin "2") (pinfunction "2_2") (pintype "passive"))
      (node (ref "C87") (pin "2") (pinfunction "2_2") (pintype "passive"))
      (node (ref "C88") (pin "2") (pinfunction "2_2") (pintype "passive"))
      (node (ref "C90") (pin "2") (pinfunction "2_2") (pintype "passive"))
      (node (ref "C92") (pin "1") (pinfunction "1_1") (pintype "passive"))
      (node (ref "C93") (pin "2") (pinfunction "2_2") (pintype "passive"))
      (node (ref "C94") (pin "2") (pinfunction "2_2") (pintype "passive"))
      (node (ref "C95") (pin "2") (pinfunction "2_2") (pintype "passive"))
      (node (ref "C96") (pin "1") (pinfunction "1_1") (pintype "passive"))
      (node (ref "C97") (pin "1") (pinfunction "1_1") (pintype "passive"))
      (node (ref "C98") (pin "2") (pinfunction "2_2") (pintype "passive"))
      (node (ref "R102") (pin "1") (pinfunction "1_1") (pintype "passive"))
      (node (ref "R104") (pin "2") (pinfunction "2_2") (pintype "passive"))
      (node (ref "R107") (pin "1") (pinfunction "1_1") (pintype "passive"))
      (node (ref "R110") (pin "2") (pinfunction "2_2") (pintype "passive"))
      (node (ref "R118") (pin "2") (pinfunction "2_2") (pintype "passive"))
      (node (ref "R125") (pin "1") (pinfunction "1_1") (pintype "passive"))
      (node (ref "R126") (pin "2") (pinfunction "2_2") (pintype "passive"))
      (node (ref "R128") (pin "2") (pinfunction "2_2") (pintype "passive"))
      (node (ref "R134") (pin "2") (pinfunction "2_2") (pintype "passive"))
      (node (ref "U4") (pin "21") (pinfunction "AGND_21") (pintype "passive"))
      (node (ref "U4") (pin "8") (pinfunction "DGND_8") (pintype "passive"))
      (node (ref "Y1") (pin "2") (pinfunction "GND_2") (pintype "passive"))
      (node (ref "Y1") (pin "4") (pinfunction "GND_4") (pintype "passive"))
    )
    (net (code "32") (name "Net-(C91-Pad1)") (class "Default")
      (node (ref "C91") (pin "1") (pinfunction "1_1") (pintype "passive"))
      (node (ref "R96") (pin "1") (pinfunction "1_1") (pintype "passive"))
      (node (ref "R97") (pin "2") (pinfunction "2_2") (pintype "passive"))
      (node (ref "R98") (pin "1") (pinfunction "1_1") (pintype "passive"))
    )
    (net (code "33") (name "Net-(C91-Pad2)") (class "Default")
      (node (ref "C91") (pin "2") (pinfunction "2_2") (pintype "passive"))
      (node (ref "R100") (pin "1") (pinfunction "1_1") (pintype "passive"))
      (node (ref "R101") (pin "2") (pinfunction "2_2") (pintype "passive"))
      (node (ref "R104") (pin "1") (pinfunction "1_1") (pintype "passive"))
    )
    (net (code "34") (name "Net-(C101-Pad1)") (class "Default")
      (node (ref "C101") (pin "1") (pinfunction "1_1") (pintype "passive"))
      (node (ref "R106") (pin "1") (pinfunction "1_1") (pintype "passive"))
      (node (ref "R112") (pin "2") (pinfunction "2_2") (pintype "passive"))
      (node (ref "R113") (pin "1") (pinfunction "1_1") (pintype "passive"))
    )
    (net (code "35") (name "Net-(C101-Pad2)") (class "Default")
      (node (ref "C101") (pin "2") (pinfunction "2_2") (pintype "passive"))
      (node (ref "R115") (pin "1") (pinfunction "1_1") (pintype "passive"))
      (node (ref "R116") (pin "2") (pinfunction "2_2") (pintype "passive"))
      (node (ref "R118") (pin "1") (pinfunction "1_1") (pintype "passive"))
    )
    (net (code "36") (name "Net-(C104-Pad1)") (class "Default")
      (node (ref "C104") (pin "1") (pinfunction "1_1") (pintype "passive"))
      (node (ref "R119") (pin "1") (pinfunction "1_1") (pintype "passive"))
      (node (ref "R120") (pin "2") (pinfunction "2_2") (pintype "passive"))
      (node (ref "R121") (pin "1") (pinfunction "1_1") (pintype "passive"))
    )
    (net (code "37") (name "Net-(C104-Pad2)") (class "Default")
      (node (ref "C104") (pin "2") (pinfunction "2_2") (pintype "passive"))
      (node (ref "R123") (pin "1") (pinfunction "1_1") (pintype "passive"))
      (node (ref "R124") (pin "2") (pinfunction "2_2") (pintype "passive"))
      (node (ref "R126") (pin "1") (pinfunction "1_1") (pintype "passive"))
    )
    (net (code "38") (name "Net-(C109-Pad1)") (class "Default")
      (node (ref "C109") (pin "1") (pinfunction "1_1") (pintype "passive"))
      (node (ref "R127") (pin "1") (pinfunction "1_1") (pintype "passive"))
      (node (ref "R129") (pin "2") (pinfunction "2_2") (pintype "passive"))
      (node (ref "R130") (pin "1") (pinfunction "1_1") (pintype "passive"))
    )
    (net (code "39") (name "Net-(C109-Pad2)") (class "Default")
      (node (ref "C109") (pin "2") (pinfunction "2_2") (pintype "passive"))
      (node (ref "R132") (pin "1") (pinfunction "1_1") (pintype "passive"))
      (node (ref "R133") (pin "2") (pinfunction "2_2") (pintype "passive"))
      (node (ref "R134") (pin "1") (pinfunction "1_1") (pintype "passive"))
    )
    (net (code "40") (name "Net-(U4-AD0{slash}~{CS}(I2S{slash}~{LJ}))") (class "Default")
      (node (ref "R105") (pin "2") (pinfunction "2_2") (pintype "passive"))
      (node (ref "U4") (pin "13") (pinfunction "AD0/~{CS}(I2S/~{LJ})_13") (pintype "passive"))
    )
    (net (code "41") (name "Net-(U4-FILT+)") (class "Default")
      (node (ref "C92") (pin "2") (pinfunction "2_2") (pintype "passive"))
      (node (ref "C93") (pin "1") (pinfunction "1_1") (pintype "passive"))
      (node (ref "U4") (pin "22") (pinfunction "FILT+_22") (pintype "passive"))
    )
    (net (code "42") (name "Net-(U4-MCLK)") (class "Default")
      (node (ref "R109") (pin "1") (pinfunction "1_1") (pintype "passive"))
      (node (ref "R111") (pin "1") (pinfunction "1_1") (pintype "passive"))
      (node (ref "U4") (pin "3") (pinfunction "MCLK_3") (pintype "passive"))
    )
    (net (code "43") (name "Net-(U4-SCL{slash}CCLK(M0))") (class "Default")
      (node (ref "R108") (pin "2") (pinfunction "2_2") (pintype "passive"))
      (node (ref "U4") (pin "11") (pinfunction "SCL/CCLK(M0)_11") (pintype "passive"))
    )
    (net (code "44") (name "Net-(U4-SDA{slash}CDIN(M1))") (class "Default")
      (node (ref "R107") (pin "2") (pinfunction "2_2") (pintype "passive"))
      (node (ref "U4") (pin "12") (pinfunction "SDA/CDIN(M1)_12") (pintype "passive"))
    )
    (net (code "45") (name "Net-(U5A-1IN+)") (class "Default")
      (node (ref "C94") (pin "1") (pinfunction "1_1") (pintype "passive"))
      (node (ref "R100") (pin "2") (pinfunction "2_2") (pintype "passive"))
      (node (ref "U5") (pin "3") (pinfunction "1IN+_3") (pintype "passive"))
    )
    (net (code "46") (name "Net-(U5A-1IN-)") (class "Default")
      (node (ref "C89") (pin "1") (pinfunction "1_1") (pintype "passive"))
      (node (ref "R98") (pin "2") (pinfunction "2_2") (pintype "passive"))
      (node (ref "U5") (pin "2") (pinfunction "1IN-_2") (pintype "passive"))
    )
    (net (code "47") (name "Net-(U5A-1OUT)") (class "Default")
      (node (ref "C89") (pin "2") (pinfunction "2_2") (pintype "passive"))
      (node (ref "R96") (pin "2") (pinfunction "2_2") (pintype "passive"))
      (node (ref "R99") (pin "1") (pinfunction "1_1") (pintype "passive"))
      (node (ref "U5") (pin "1") (pinfunction "1OUT_1") (pintype "passive"))
    )
    (net (code "48") (name "Net-(U5B-2IN+)") (class "Default")
      (node (ref "C102") (pin "1") (pinfunction "1_1") (pintype "passive"))
      (node (ref "R115") (pin "2") (pinfunction "2_2") (pintype "passive"))
      (node (ref "U5") (pin "5") (pinfunction "2IN+_5") (pintype "passive"))
    )
    (net (code "49") (name "Net-(U5B-2IN-)") (class "Default")
      (node (ref "C99") (pin "1") (pinfunction "1_1") (pintype "passive"))
      (node (ref "R113") (pin "2") (pinfunction "2_2") (pintype "passive"))
      (node (ref "U5") (pin "6") (pinfunction "2IN-_6") (pintype "passive"))
    )
    (net (code "50") (name "Net-(U5B-2OUT)") (class "Default")
      (node (ref "C99") (pin "2") (pinfunction "2_2") (pintype "passive"))
      (node (ref "R106") (pin "2") (pinfunction "2_2") (pintype "passive"))
      (node (ref "R114") (pin "1") (pinfunction "1_1") (pintype "passive"))
      (node (ref "U5") (pin "7") (pinfunction "2OUT_7") (pintype "passive"))
    )
    (net (code "51") (name "Net-(U6A-1IN+)") (class "Default")
      (node (ref "C105") (pin "1") (pinfunction "1_1") (pintype "passive"))
      (node (ref "R123") (pin "2") (pinfunction "2_2") (pintype "passive"))
      (node (ref "U6") (pin "3") (pinfunction "1IN+_3") (pintype "passive"))
    )
    (net (code "52") (name "Net-(U6A-1IN-)") (class "Default")
      (node (ref "C103") (pin "1") (pinfunction "1_1") (pintype "passive"))
      (node (ref "R121") (pin "2") (pinfunction "2_2") (pintype "passive"))
      (node (ref "U6") (pin "2") (pinfunction "1IN-_2") (pintype "passive"))
    )
    (net (code "53") (name "Net-(U6A-1OUT)") (class "Default")
      (node (ref "C103") (pin "2") (pinfunction "2_2") (pintype "passive"))
      (node (ref "R119") (pin "2") (pinfunction "2_2") (pintype "passive"))
      (node (ref "R122") (pin "1") (pinfunction "1_1") (pintype "passive"))
      (node (ref "U6") (pin "1") (pinfunction "1OUT_1") (pintype "passive"))
    )
    (net (code "54") (name "Net-(U6B-2IN+)") (class "Default")
      (node (ref "C110") (pin "1") (pinfunction "1_1") (pintype "passive"))
      (node (ref "R132") (pin "2") (pinfunction "2_2") (pintype "passive"))
      (node (ref "U6") (pin "5") (pinfunction "2IN+_5") (pintype "passive"))
    )
    (net (code "55") (name "Net-(U6B-2IN-)") (class "Default")
      (node (ref "C107") (pin "1") (pinfunction "1_1") (pintype "passive"))
      (node (ref "R130") (pin "2") (pinfunction "2_2") (pintype "passive"))
      (node (ref "U6") (pin "6") (pinfunction "2IN-_6") (pintype "passive"))
    )
    (net (code "56") (name "Net-(U6B-2OUT)") (class "Default")
      (node (ref "C107") (pin "2") (pinfunction "2_2") (pintype "passive"))
      (node (ref "R127") (pin "2") (pinfunction "2_2") (pintype "passive"))
      (node (ref "R131") (pin "1") (pinfunction "1_1") (pintype "passive"))
      (node (ref "U6") (pin "7") (pinfunction "2OUT_7") (pintype "passive"))
    )
    (net (code "57") (name "unconnected-(U4-~{AMUTEC}-Pad23)") (class "Default")
      (node (ref "U4") (pin "23") (pinfunction "~{AMUTEC}_23") (pintype "passive+no_connect"))
    )
    (net (code "58") (name "unconnected-(U4-~{BMUTEC}-Pad28)") (class "Default")
      (node (ref "U4") (pin "28") (pinfunction "~{BMUTEC}_28") (pintype "passive+no_connect"))
    )
  )
)
